# Power.net
KiCad netlist of a schematic drawn in Altium Designer
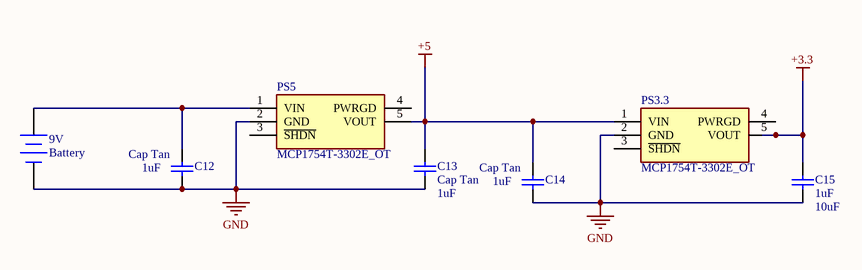
[diagram p0: Power.SchDoc]

(export (version "E")
  (design (tool "Eeschema 10.0.6"))
  (components
    (comp (ref "9V")
      (value "Battery")
      (footprint "BAT-2")
      (description "Multicell Battery")
      (fields (field (name "PUBLISHER") "Altium Limited"))
      (libsource (lib "Miscellaneous Devices") (part "Battery"))
    )
    (comp (ref "C12")
      (value "Cap Tan")
      (footprint "1608[0603]")
      (description "Capacitor (Semiconductor SIM Model)")
      (fields (field (name "ALTIUM_VALUE") "1uF") (field (name "PUBLISHER") "Altium Limited"))
      (libsource (lib "Miscellaneous Devices") (part "Cap Semi"))
    )
    (comp (ref "C13")
      (value "Cap Tan")
      (footprint "1608[0603]")
      (description "Capacitor (Semiconductor SIM Model)")
      (fields (field (name "ALTIUM_VALUE") "1uF") (field (name "PUBLISHER") "Altium Limited"))
      (libsource (lib "Miscellaneous Devices") (part "Cap Semi"))
    )
    (comp (ref "C14")
      (value "Cap Tan")
      (footprint "1608[0603]")
      (description "Capacitor (Semiconductor SIM Model)")
      (fields (field (name "ALTIUM_VALUE") "1uF") (field (name "PUBLISHER") "Altium Limited"))
      (libsource (lib "Miscellaneous Devices") (part "Cap Semi"))
    )
    (comp (ref "C15")
      (value "1uF")
      (footprint "1608[0603]")
      (description "Capacitor (Semiconductor SIM Model)")
      (fields (field (name "ALTIUM_VALUE") "10uF") (field (name "PUBLISHER") "Altium Limited"))
      (libsource (lib "Miscellaneous Devices") (part "Cap Semi"))
    )
    (comp (ref "PS3.3")
      (value "MCP1754T-3302E_OT")
      (footprint "SamacSys:SOT95P270X145-5N")
      (description "Power Supply")
      (fields
        (field (name "MANUFACTURER_PART_NUMBER") "MCP1754T-3302E/OT")
        (field (name "MOUSER PART NUMBER") "579-MCP1754T3302EOT")
      )
      (libsource (lib "*") (part "MCP1754T-3302E_OT"))
    )
    (comp (ref "PS5")
      (value "MCP1754T-3302E_OT")
      (footprint "SamacSys:SOT95P270X145-5N")
      (description "Power Supply")
      (fields
        (field (name "MANUFACTURER_PART_NUMBER") "MCP1754T-3302E/OT")
        (field (name "MOUSER PART NUMBER") "579-MCP1754T3302EOT")
      )
      (libsource (lib "*") (part "MCP1754T-3302E_OT"))
    )
  )
  (nets
    (net (code "1") (name "+3.3") (class "Default")
      (node (ref "C15") (pin "1") (pinfunction "1_1") (pintype "passive"))
      (node (ref "PS3.3") (pin "5") (pinfunction "VOUT_5") (pintype "passive"))
    )
    (net (code "2") (name "+5") (class "Default")
      (node (ref "C13") (pin "1") (pinfunction "1_1") (pintype "passive"))
      (node (ref "C14") (pin "2") (pinfunction "2_2") (pintype "passive"))
      (node (ref "PS3.3") (pin "1") (pinfunction "VIN_1") (pintype "passive"))
      (node (ref "PS5") (pin "5") (pinfunction "VOUT_5") (pintype "passive"))
    )
    (net (code "3") (name "GND") (class "Default")
      (node (ref "9V") (pin "2") (pinfunction "-_2") (pintype "passive"))
      (node (ref "C12") (pin "1") (pinfunction "1_1") (pintype "passive"))
      (node (ref "C13") (pin "2") (pinfunction "2_2") (pintype "passive"))
      (node (ref "C14") (pin "1") (pinfunction "1_1") (pintype "passive"))
      (node (ref "C15") (pin "2") (pinfunction "2_2") (pintype "passive"))
      (node (ref "PS3.3") (pin "2") (pinfunction "GND_2") (pintype "passive"))
      (node (ref "PS5") (pin "2") (pinfunction "GND_2") (pintype "passive"))
    )
    (net (code "4") (name "Net-(9V-+)") (class "Default")
      (node (ref "9V") (pin "1") (pinfunction "+_1") (pintype "passive"))
      (node (ref "C12") (pin "2") (pinfunction "2_2") (pintype "passive"))
      (node (ref "PS5") (pin "1") (pinfunction "VIN_1") (pintype "passive"))
    )
    (net (code "5") (name "unconnected-(PS3.3-PWRGD-Pad4)") (class "Default")
      (node (ref "PS3.3") (pin "4") (pinfunction "PWRGD_4") (pintype "passive"))
    )
    (net (code "6") (name "unconnected-(PS3.3-~{SHDN}-Pad3)") (class "Default")
      (node (ref "PS3.3") (pin "3") (pinfunction "~{SHDN}_3") (pintype "passive"))
    )
    (net (code "7") (name "unconnected-(PS5-PWRGD-Pad4)") (class "Default")
      (node (ref "PS5") (pin "4") (pinfunction "PWRGD_4") (pintype "passive"))
    )
    (net (code "8") (name "unconnected-(PS5-~{SHDN}-Pad3)") (class "Default")
      (node (ref "PS5") (pin "3") (pinfunction "~{SHDN}_3") (pintype "passive"))
    )
  )
)
